# Sheet2.net
KiCad netlist of a schematic drawn in Altium Designer
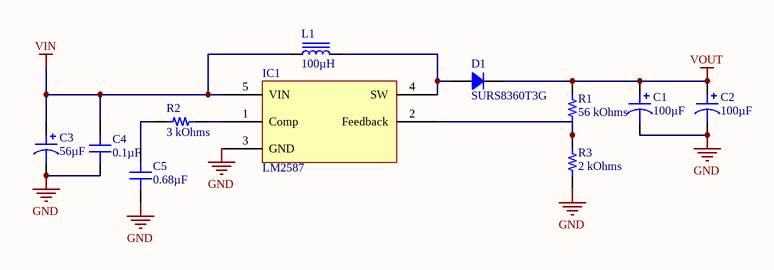
[diagram p0: Sheet2.SchDoc]

(export (version "E")
  (design (tool "Eeschema 10.0.6"))
  (components
    (comp (ref "C1")
      (value "100µF")
      (footprint "CAP ALSMD 8.3MM H10.5MM")
      (description "CAP ALUM 100UF 20% 50V SMD")
      (fields
        (field (name "PART NUMBER") "EEE-FK1H101P")
        (field (name "MANUFACTURER") "Panasonic Electronic Components")
      )
      (libsource (lib "Celestial Altium Library - altium_library") (part "Polarised Capacitor"))
    )
    (comp (ref "C2")
      (value "100µF")
      (footprint "CAP ALSMD 8.3MM H10.5MM")
      (description "CAP ALUM 100UF 20% 50V SMD")
      (fields
        (field (name "PART NUMBER") "EEE-FK1H101P")
        (field (name "MANUFACTURER") "Panasonic Electronic Components")
      )
      (libsource (lib "Celestial Altium Library - altium_library") (part "Polarised Capacitor"))
    )
    (comp (ref "C3")
      (value "56µF")
      (footprint "CAP ALSMD 6.6MM H7.7MM")
      (description "CAP ALUM 56UF 20% 35V SMD")
      (fields (field (name "PART NUMBER") "UUD1V560MCL1GS") (field (name "MANUFACTURER") "Nichicon"))
      (libsource (lib "Celestial Altium Library - altium_library") (part "Polarised Capacitor"))
    )
    (comp (ref "C4")
      (value "0.1µF")
      (footprint "CAP 0805_2012")
      (description "CAP CER 0805 10% X8R 50V 100NF")
      (fields (field (name "PART NUMBER") "AC0805KKX8R9BB104") (field (name "MANUFACTURER") "Yageo"))
      (libsource (lib "Celestial Altium Library - altium_library") (part "Capacitor"))
    )
    (comp (ref "C5")
      (value "0.68µF")
      (footprint "CAP 0805_2012")
      (description "CAP CER 0.68UF 16V X7R 0805")
      (fields (field (name "PART NUMBER") "CC0805KKX7R7BB684") (field (name "MANUFACTURER") "Yageo"))
      (libsource (lib "Celestial Altium Library - altium_library") (part "Capacitor"))
    )
    (comp (ref "D1")
      (value "SURS8360T3G")
      (footprint "DO214AB SMC")
      (description "DIODE GEN PURP 600V 3A SMC")
      (fields (field (name "MANUFACTURER") "ON Semiconductor"))
      (libsource (lib "Celestial Altium Library - altium_library") (part "Diode"))
    )
    (comp (ref "IC1")
      (value "LM2587")
      (footprint "AltiumLive:D2PAK")
      (description "Boost Converter")
      (libsource (lib "AltiumLive") (part "LM2587"))
    )
    (comp (ref "L1")
      (value "100µH")
      (footprint "7447070")
      (description "FIXED IND 100UH 2.1A 150MOHM SMD")
      (fields (field (name "PART NUMBER") "SRR1280-101M") (field (name "MANUFACTURER") "Bourns Inc."))
      (libsource (lib "Celestial Altium Library - altium_library") (part "Inductor"))
    )
    (comp (ref "R1")
      (value "56 kOhms")
      (footprint "RES 0805_2012")
      (description "RES SMD 56K OHM 5% 1/8W 0805")
      (fields (field (name "PART NUMBER") "RC0805JR-0756KL") (field (name "MANUFACTURER") "Yageo"))
      (libsource (lib "Celestial Altium Library - altium_library") (part "Resistor"))
    )
    (comp (ref "R2")
      (value "3 kOhms")
      (footprint "RES 0805_2012")
      (description "RES SMD 3K OHM 0.5% 1/8W 0805")
      (fields (field (name "PART NUMBER") "RT0805DRD073KL") (field (name "MANUFACTURER") "Yageo"))
      (libsource (lib "Celestial Altium Library - altium_library") (part "Resistor"))
    )
    (comp (ref "R3")
      (value "2 kOhms")
      (footprint "RES 0805_2012")
      (description "RES SMD 2K OHM 1% 1/8W 0805")
      (fields (field (name "PART NUMBER") "AC0805FR-072KL") (field (name "MANUFACTURER") "Yageo"))
      (libsource (lib "Celestial Altium Library - altium_library") (part "Resistor"))
    )
  )
  (nets
    (net (code "1") (name "GND") (class "Default")
      (node (ref "C1") (pin "2") (pinfunction "2_2") (pintype "passive"))
      (node (ref "C2") (pin "2") (pinfunction "2_2") (pintype "passive"))
      (node (ref "C3") (pin "2") (pinfunction "2_2") (pintype "passive"))
      (node (ref "C4") (pin "1") (pinfunction "1_1") (pintype "passive"))
      (node (ref "C5") (pin "1") (pinfunction "1_1") (pintype "passive"))
      (node (ref "IC1") (pin "3") (pinfunction "GND_3") (pintype "passive"))
      (node (ref "R3") (pin "1") (pinfunction "1_1") (pintype "passive"))
    )
    (net (code "2") (name "Net-(C5-Pad2)") (class "Default")
      (node (ref "C5") (pin "2") (pinfunction "2_2") (pintype "passive"))
      (node (ref "R2") (pin "1") (pinfunction "1_1") (pintype "passive"))
    )
    (net (code "3") (name "Net-(IC1-Comp)") (class "Default")
      (node (ref "IC1") (pin "1") (pinfunction "Comp_1") (pintype "passive"))
      (node (ref "R2") (pin "2") (pinfunction "2_2") (pintype "passive"))
    )
    (net (code "4") (name "Net-(IC1-Feedback)") (class "Default")
      (node (ref "IC1") (pin "2") (pinfunction "Feedback_2") (pintype "passive"))
      (node (ref "R1") (pin "1") (pinfunction "1_1") (pintype "passive"))
      (node (ref "R3") (pin "2") (pinfunction "2_2") (pintype "passive"))
    )
    (net (code "5") (name "Net-(IC1-SW)") (class "Default")
      (node (ref "D1") (pin "1") (pinfunction "1_1") (pintype "passive"))
      (node (ref "IC1") (pin "4") (pinfunction "SW_4") (pintype "passive"))
      (node (ref "L1") (pin "2") (pinfunction "2_2") (pintype "passive"))
    )
    (net (code "6") (name "VIN") (class "Default")
      (node (ref "C3") (pin "1") (pinfunction "1_1") (pintype "passive"))
      (node (ref "C4") (pin "2") (pinfunction "2_2") (pintype "passive"))
      (node (ref "IC1") (pin "5") (pinfunction "VIN_5") (pintype "passive"))
      (node (ref "L1") (pin "1") (pinfunction "1_1") (pintype "passive"))
    )
    (net (code "7") (name "VOUT") (class "Default")
      (node (ref "C1") (pin "1") (pinfunction "1_1") (pintype "passive"))
      (node (ref "C2") (pin "1") (pinfunction "1_1") (pintype "passive"))
      (node (ref "D1") (pin "2") (pinfunction "2_2") (pintype "passive"))
      (node (ref "R1") (pin "2") (pinfunction "2_2") (pintype "passive"))
    )
  )
)
